# rgbshCORECCTED.net
KiCad netlist of a schematic drawn in EAGLE
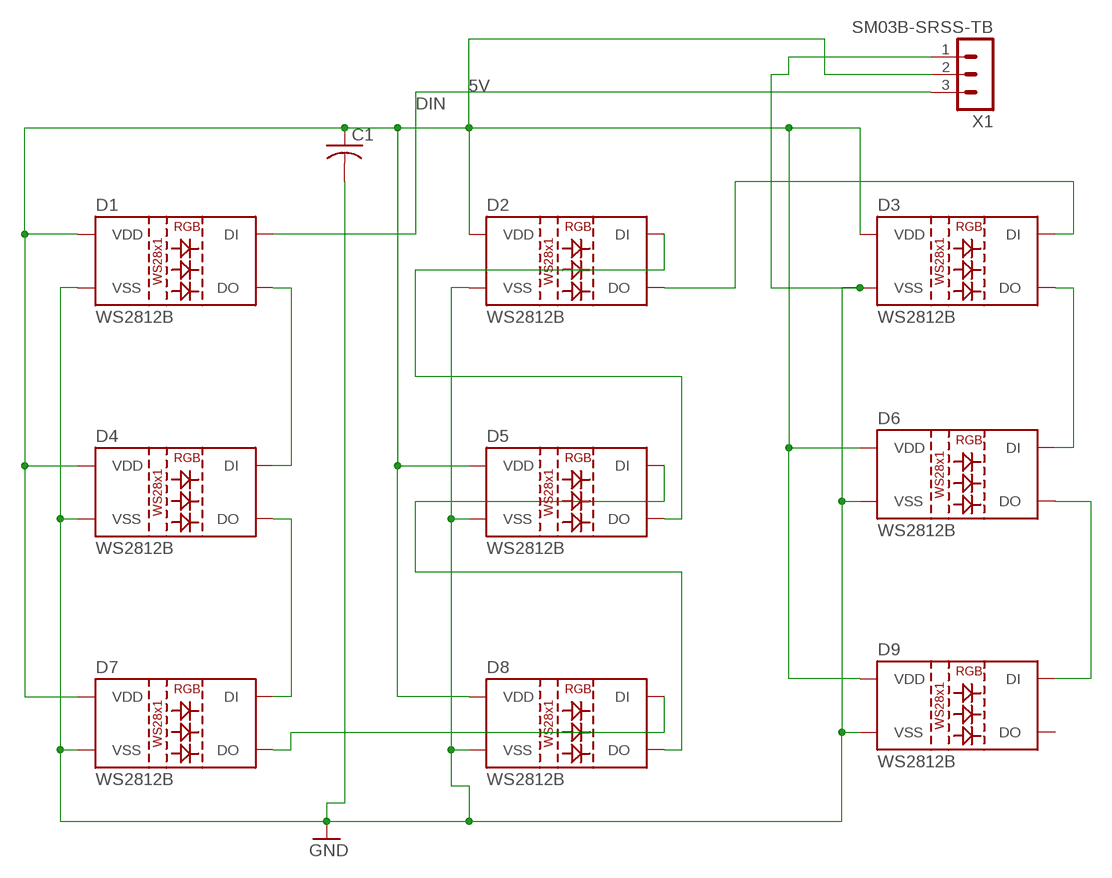
[diagram p0: schematic, sheet 1]

(export (version "E")
  (design (tool "Eeschema 10.0.6"))
  (components
    (comp (ref "C1")
      (value "C-USC0805K")
      (footprint "eagle-import:C0805K")
      (libsource (lib "eagle-import") (part "C-USC0805K"))
    )
    (comp (ref "D1")
      (value "WS2812B")
      (footprint "eagle-import:WS2812B")
      (libsource (lib "eagle-import") (part "WS2812B"))
    )
    (comp (ref "D2")
      (value "WS2812B")
      (footprint "eagle-import:WS2812B")
      (libsource (lib "eagle-import") (part "WS2812B"))
    )
    (comp (ref "D3")
      (value "WS2812B")
      (footprint "eagle-import:WS2812B")
      (libsource (lib "eagle-import") (part "WS2812B"))
    )
    (comp (ref "D4")
      (value "WS2812B")
      (footprint "eagle-import:WS2812B")
      (libsource (lib "eagle-import") (part "WS2812B"))
    )
    (comp (ref "D5")
      (value "WS2812B")
      (footprint "eagle-import:WS2812B")
      (libsource (lib "eagle-import") (part "WS2812B"))
    )
    (comp (ref "D6")
      (value "WS2812B")
      (footprint "eagle-import:WS2812B")
      (libsource (lib "eagle-import") (part "WS2812B"))
    )
    (comp (ref "D7")
      (value "WS2812B")
      (footprint "eagle-import:WS2812B")
      (libsource (lib "eagle-import") (part "WS2812B"))
    )
    (comp (ref "D8")
      (value "WS2812B")
      (footprint "eagle-import:WS2812B")
      (libsource (lib "eagle-import") (part "WS2812B"))
    )
    (comp (ref "D9")
      (value "WS2812B")
      (footprint "eagle-import:WS2812B")
      (libsource (lib "eagle-import") (part "WS2812B"))
    )
    (comp (ref "X1")
      (value "SM03B-SRSS-TB")
      (footprint "eagle-import:SM03B-SRSS-TB")
      (libsource (lib "eagle-import") (part "SM03B-SRSS-TB"))
    )
  )
  (nets
    (net (code "1") (name "/5V") (class "Default")
      (node (ref "C1") (pin "1") (pinfunction "1_1") (pintype "passive"))
      (node (ref "D1") (pin "1") (pinfunction "VDD_1") (pintype "bidirectional"))
      (node (ref "D2") (pin "1") (pinfunction "VDD_1") (pintype "bidirectional"))
      (node (ref "D3") (pin "1") (pinfunction "VDD_1") (pintype "bidirectional"))
      (node (ref "D4") (pin "1") (pinfunction "VDD_1") (pintype "bidirectional"))
      (node (ref "D5") (pin "1") (pinfunction "VDD_1") (pintype "bidirectional"))
      (node (ref "D6") (pin "1") (pinfunction "VDD_1") (pintype "bidirectional"))
      (node (ref "D7") (pin "1") (pinfunction "VDD_1") (pintype "bidirectional"))
      (node (ref "D8") (pin "1") (pinfunction "VDD_1") (pintype "bidirectional"))
      (node (ref "D9") (pin "1") (pinfunction "VDD_1") (pintype "bidirectional"))
      (node (ref "X1") (pin "2") (pinfunction "2_2") (pintype "passive"))
    )
    (net (code "2") (name "/DIN") (class "Default")
      (node (ref "D1") (pin "4") (pinfunction "DI_4") (pintype "bidirectional"))
      (node (ref "X1") (pin "3") (pinfunction "3_3") (pintype "passive"))
    )
    (net (code "3") (name "GND") (class "Default")
      (node (ref "C1") (pin "2") (pinfunction "2_2") (pintype "passive"))
      (node (ref "D1") (pin "3") (pinfunction "VSS_3") (pintype "bidirectional"))
      (node (ref "D2") (pin "3") (pinfunction "VSS_3") (pintype "bidirectional"))
      (node (ref "D3") (pin "3") (pinfunction "VSS_3") (pintype "bidirectional"))
      (node (ref "D4") (pin "3") (pinfunction "VSS_3") (pintype "bidirectional"))
      (node (ref "D5") (pin "3") (pinfunction "VSS_3") (pintype "bidirectional"))
      (node (ref "D6") (pin "3") (pinfunction "VSS_3") (pintype "bidirectional"))
      (node (ref "D7") (pin "3") (pinfunction "VSS_3") (pintype "bidirectional"))
      (node (ref "D8") (pin "3") (pinfunction "VSS_3") (pintype "bidirectional"))
      (node (ref "D9") (pin "3") (pinfunction "VSS_3") (pintype "bidirectional"))
      (node (ref "X1") (pin "1") (pinfunction "1_1") (pintype "passive"))
    )
    (net (code "4") (name "Net-(D1-DO)") (class "Default")
      (node (ref "D1") (pin "2") (pinfunction "DO_2") (pintype "bidirectional"))
      (node (ref "D4") (pin "4") (pinfunction "DI_4") (pintype "bidirectional"))
    )
    (net (code "5") (name "Net-(D2-DI)") (class "Default")
      (node (ref "D2") (pin "4") (pinfunction "DI_4") (pintype "bidirectional"))
      (node (ref "D5") (pin "2") (pinfunction "DO_2") (pintype "bidirectional"))
    )
    (net (code "6") (name "Net-(D2-DO)") (class "Default")
      (node (ref "D2") (pin "2") (pinfunction "DO_2") (pintype "bidirectional"))
      (node (ref "D3") (pin "4") (pinfunction "DI_4") (pintype "bidirectional"))
    )
    (net (code "7") (name "Net-(D3-DO)") (class "Default")
      (node (ref "D3") (pin "2") (pinfunction "DO_2") (pintype "bidirectional"))
      (node (ref "D6") (pin "4") (pinfunction "DI_4") (pintype "bidirectional"))
    )
    (net (code "8") (name "Net-(D4-DO)") (class "Default")
      (node (ref "D4") (pin "2") (pinfunction "DO_2") (pintype "bidirectional"))
      (node (ref "D7") (pin "4") (pinfunction "DI_4") (pintype "bidirectional"))
    )
    (net (code "9") (name "Net-(D5-DI)") (class "Default")
      (node (ref "D5") (pin "4") (pinfunction "DI_4") (pintype "bidirectional"))
      (node (ref "D8") (pin "2") (pinfunction "DO_2") (pintype "bidirectional"))
    )
    (net (code "10") (name "Net-(D6-DO)") (class "Default")
      (node (ref "D6") (pin "2") (pinfunction "DO_2") (pintype "bidirectional"))
      (node (ref "D9") (pin "4") (pinfunction "DI_4") (pintype "bidirectional"))
    )
    (net (code "11") (name "Net-(D7-DO)") (class "Default")
      (node (ref "D7") (pin "2") (pinfunction "DO_2") (pintype "bidirectional"))
      (node (ref "D8") (pin "4") (pinfunction "DI_4") (pintype "bidirectional"))
    )
    (net (code "12") (name "unconnected-(D9-DO-Pad2)") (class "Default")
      (node (ref "D9") (pin "2") (pinfunction "DO_2") (pintype "bidirectional"))
    )
  )
)
